# Synth.net
KiCad netlist of a schematic drawn in Altium Designer
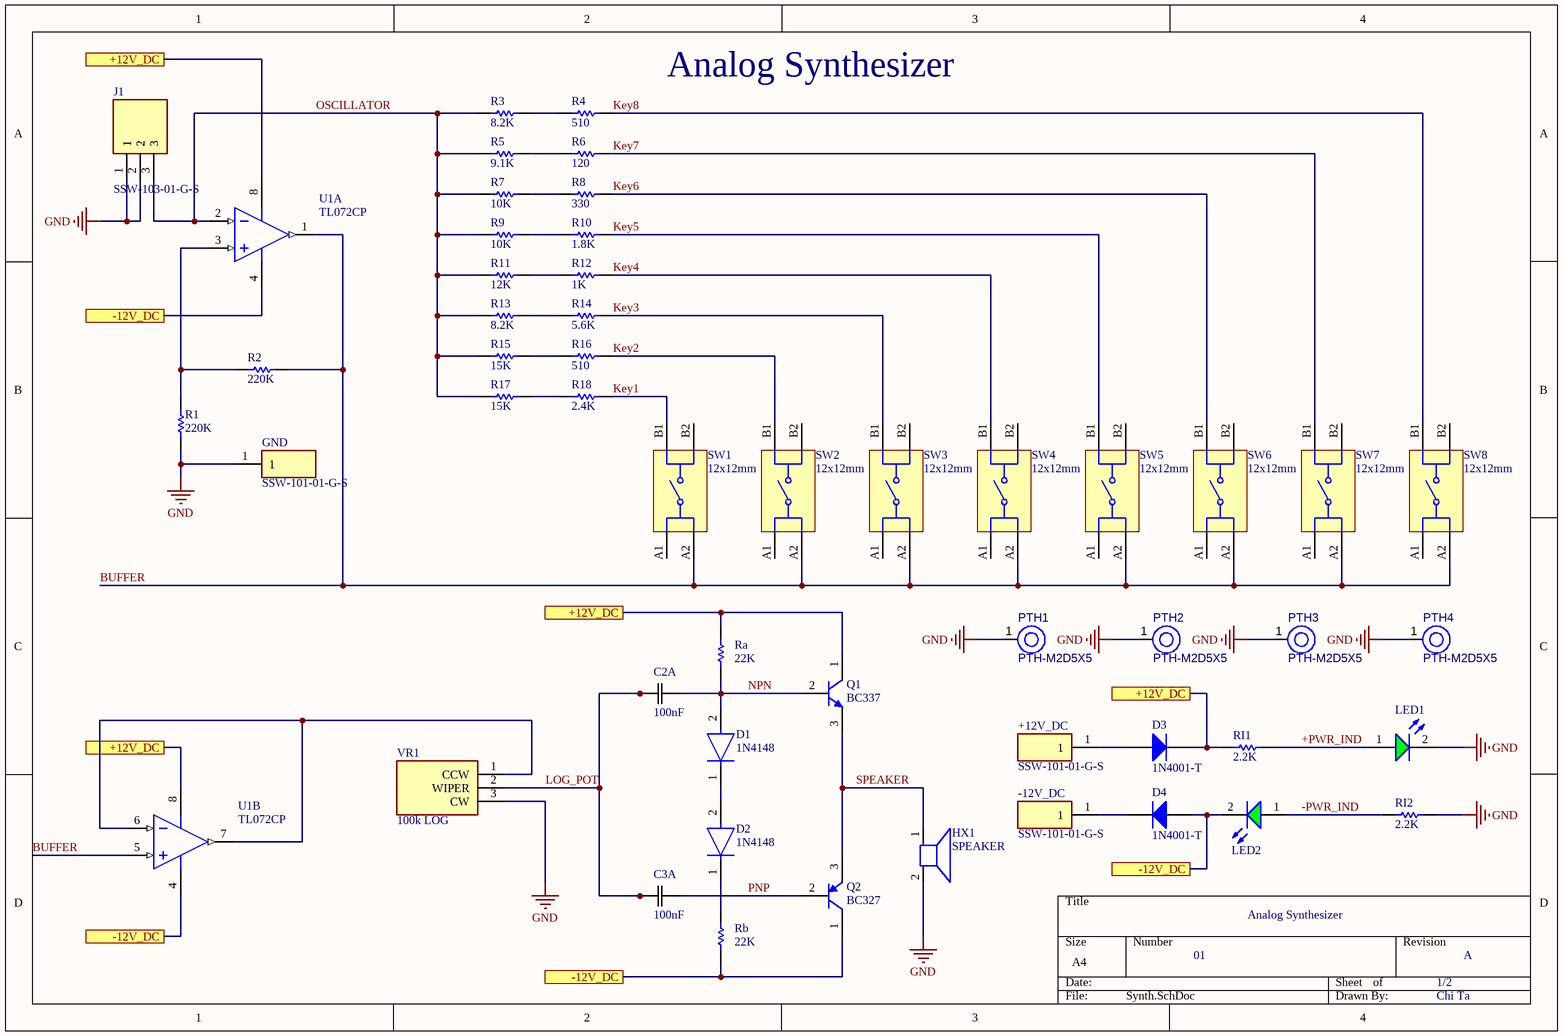
[diagram p0: Synth.SchDoc]

(export (version "E")
  (design (tool "Eeschema 10.0.6"))
  (components
    (comp (ref "+12V_DC")
      (value "SSW-101-01-G-S")
      (footprint "SamacSys:SSW-101-XX-YYY-S")
      (description "Connector")
      (fields (field (name "MOUSER PART NUMBER") "200-SSW10101GS"))
      (libsource (lib "*") (part "SSW-101-01-G-S"))
    )
    (comp (ref "-12V_DC")
      (value "SSW-101-01-G-S")
      (footprint "SamacSys:SSW-101-XX-YYY-S")
      (description "Connector")
      (fields (field (name "MOUSER PART NUMBER") "200-SSW10101GS"))
      (libsource (lib "*") (part "SSW-101-01-G-S"))
    )
    (comp (ref "C2")
      (value "100nF")
      (footprint "CAP_MKT1817_7p2x2p5x6p5-5_VIS")
      (description "MKT1817410064W")
      (libsource (lib "TMU") (part "MKT1817410064W"))
    )
    (comp (ref "C3")
      (value "100nF")
      (footprint "CAP_MKT1817_7p2x2p5x6p5-5_VIS")
      (description "MKT1817410064W")
      (libsource (lib "TMU") (part "MKT1817410064W"))
    )
    (comp (ref "D1")
      (value "1N4148")
      (footprint "FP-017AG-MFG")
      (description "DIODE GEN PURP 100V 200MA DO35")
      (fields (field (name "VOLTAGE") "100V"))
      (libsource (lib "Altium Content Vault") (part "d7152d700b627762746794eb795d46e"))
    )
    (comp (ref "D2")
      (value "1N4148")
      (footprint "FP-017AG-MFG")
      (description "DIODE GEN PURP 100V 200MA DO35")
      (fields (field (name "VOLTAGE") "100V"))
      (libsource (lib "Altium Content Vault") (part "d7152d700b627762746794eb795d46e"))
    )
    (comp (ref "D3")
      (value "1N4001-T")
      (footprint "DIOD-DO-41-P-2_V")
      (description "1.0 A Rectifier, 15 pF, 50 V, -65 to 150 degC, 2-Pin DO-41 Plastic, RoHS, Tape and Reel")
      (fields (field (name "MANUFACTURER") "Diodes Inc"))
      (libsource (lib "Altium Content Vault") (part "DIOD-D-A1K2-2"))
    )
    (comp (ref "D4")
      (value "1N4001-T")
      (footprint "DIOD-DO-41-P-2_V")
      (description "1.0 A Rectifier, 15 pF, 50 V, -65 to 150 degC, 2-Pin DO-41 Plastic, RoHS, Tape and Reel")
      (fields (field (name "MANUFACTURER") "Diodes Inc"))
      (libsource (lib "Altium Content Vault") (part "DIOD-D-A1K2-2"))
    )
    (comp (ref "GND")
      (value "SSW-101-01-G-S")
      (footprint "SamacSys:SSW-101-XX-YYY-S")
      (description "Connector")
      (fields (field (name "MOUSER PART NUMBER") "200-SSW10101GS"))
      (libsource (lib "") (part "SSW-101-01-G-S_1"))
    )
    (comp (ref "HX1")
      (value "SPEAKER")
      (footprint "AL60P")
      (description "8 Ohms Low Profile Speaker 250mW 380Hz ~ 10kHz Top Round 93dB")
      (fields (field (name "MF") "Texas Instruments"))
      (libsource (lib "TMU") (part "SPEAKER"))
    )
    (comp (ref "J1")
      (value "SSW-103-01-G-S")
      (footprint "SamacSys:RHDR3W64P0X254_1X3_813X241X851P")
      (description "Connector")
      (fields (field (name "MOUSER PART NUMBER") "200-SSW10301GS"))
      (libsource (lib "*") (part "SSW-103-01-G-S"))
    )
    (comp (ref "LED1")
      (value "151031VS04000")
      (footprint "WL-TMRC_D3.95H5.3")
      (libsource (lib "Altium Content Vault") (part "LED_Green_1A-2K"))
    )
    (comp (ref "LED2")
      (value "151031VS04000")
      (footprint "WL-TMRC_D3.95H5.3")
      (libsource (lib "Altium Content Vault") (part "LED_Green_1A-2K"))
    )
    (comp (ref "PTH1")
      (value "PTH-M2D5X5")
      (footprint "PTH-M2D5X5")
      (description "M2 PTH (2.5mm), 5mm pad")
      (libsource (lib "TMU") (part "CMP-00028-00000-1"))
    )
    (comp (ref "PTH2")
      (value "PTH-M2D5X5")
      (footprint "PTH-M2D5X5")
      (description "M2 PTH (2.5mm), 5mm pad")
      (libsource (lib "TMU") (part "CMP-00028-00000-1"))
    )
    (comp (ref "PTH3")
      (value "PTH-M2D5X5")
      (footprint "PTH-M2D5X5")
      (description "M2 PTH (2.5mm), 5mm pad")
      (libsource (lib "TMU") (part "CMP-00028-00000-1"))
    )
    (comp (ref "PTH4")
      (value "PTH-M2D5X5")
      (footprint "PTH-M2D5X5")
      (description "M2 PTH (2.5mm), 5mm pad")
      (libsource (lib "TMU") (part "CMP-00028-00000-1"))
    )
    (comp (ref "Q1")
      (value "BC337")
      (footprint "ONSC-TO-92-3-29-11_AM_BL")
      (description "Amplifier Transistor, NPN Silicon, 3-Pin TO-92, Pb-Free, Ammo Box")
      (fields (field (name "PARTNUMBER") "BC337-40ZL1G") (field (name "MANUFACTURER") "On Semiconductor"))
      (libsource (lib "Altium Content Vault") (part "ONSC-NPN-C1B2E3-3"))
    )
    (comp (ref "Q2")
      (value "BC327")
      (footprint "ONSC-TO-92-3-29-11_AM_BL")
      (description "Amplifier Transistor, PNP Silicon, 3-Pin TO-92, Pb-Free, Ammo Box")
      (fields (field (name "MANUFACTURER") "On Semiconductor") (field (name "PARTNUMBER") "BC327-25ZL1G"))
      (libsource (lib "Altium Content Vault") (part "ONSC-PNP-C1B2E3-3"))
    )
    (comp (ref "R1")
      (value "220K")
      (footprint "RESA60-630X240")
      (description "Axial Resistor, 10 KOhm, +/- 1%, 0.25 W, -55 to 155 degC, 2-Pin THD, RoHS, Bulk")
      (fields (field (name "TOLERANCE") "1%") (field (name "MANUFACTURER") "Yageo"))
      (libsource (lib "Altium Content Vault") (part "RES-2"))
    )
    (comp (ref "R2")
      (value "220K")
      (footprint "RESA60-630X240")
      (description "Axial Resistor, 10 KOhm, +/- 1%, 0.25 W, -55 to 155 degC, 2-Pin THD, RoHS, Bulk")
      (fields (field (name "TOLERANCE") "1%") (field (name "MANUFACTURER") "Yageo"))
      (libsource (lib "Altium Content Vault") (part "RES-2"))
    )
    (comp (ref "R3")
      (value "8.2K")
      (footprint "RESA60-630X240")
      (description "Axial Resistor, 10 KOhm, +/- 1%, 0.25 W, -55 to 155 degC, 2-Pin THD, RoHS, Bulk")
      (fields (field (name "TOLERANCE") "1%") (field (name "MANUFACTURER") "Yageo"))
      (libsource (lib "Altium Content Vault") (part "RES-2"))
    )
    (comp (ref "R4")
      (value "510")
      (footprint "RESA60-630X240")
      (description "Axial Resistor, 10 KOhm, +/- 1%, 0.25 W, -55 to 155 degC, 2-Pin THD, RoHS, Bulk")
      (fields (field (name "TOLERANCE") "1%") (field (name "MANUFACTURER") "Yageo"))
      (libsource (lib "Altium Content Vault") (part "RES-2"))
    )
    (comp (ref "R5")
      (value "9.1K")
      (footprint "RESA60-630X240")
      (description "Axial Resistor, 10 KOhm, +/- 1%, 0.25 W, -55 to 155 degC, 2-Pin THD, RoHS, Bulk")
      (fields (field (name "TOLERANCE") "1%") (field (name "MANUFACTURER") "Yageo"))
      (libsource (lib "Altium Content Vault") (part "RES-2"))
    )
    (comp (ref "R6")
      (value "120")
      (footprint "RESA60-630X240")
      (description "Axial Resistor, 10 KOhm, +/- 1%, 0.25 W, -55 to 155 degC, 2-Pin THD, RoHS, Bulk")
      (fields (field (name "TOLERANCE") "1%") (field (name "MANUFACTURER") "Yageo"))
      (libsource (lib "Altium Content Vault") (part "RES-2"))
    )
    (comp (ref "R7")
      (value "10K")
      (footprint "RESA60-630X240")
      (description "Axial Resistor, 10 KOhm, +/- 1%, 0.25 W, -55 to 155 degC, 2-Pin THD, RoHS, Bulk")
      (fields (field (name "TOLERANCE") "1%") (field (name "MANUFACTURER") "Yageo"))
      (libsource (lib "Altium Content Vault") (part "RES-2"))
    )
    (comp (ref "R8")
      (value "330")
      (footprint "RESA60-630X240")
      (description "Axial Resistor, 10 KOhm, +/- 1%, 0.25 W, -55 to 155 degC, 2-Pin THD, RoHS, Bulk")
      (fields (field (name "TOLERANCE") "1%") (field (name "MANUFACTURER") "Yageo"))
      (libsource (lib "Altium Content Vault") (part "RES-2"))
    )
    (comp (ref "R9")
      (value "10K")
      (footprint "RESA60-630X240")
      (description "Axial Resistor, 10 KOhm, +/- 1%, 0.25 W, -55 to 155 degC, 2-Pin THD, RoHS, Bulk")
      (fields (field (name "TOLERANCE") "1%") (field (name "MANUFACTURER") "Yageo"))
      (libsource (lib "Altium Content Vault") (part "RES-2"))
    )
    (comp (ref "R10")
      (value "1.8K")
      (footprint "RESA60-630X240")
      (description "Axial Resistor, 10 KOhm, +/- 1%, 0.25 W, -55 to 155 degC, 2-Pin THD, RoHS, Bulk")
      (fields (field (name "TOLERANCE") "1%") (field (name "MANUFACTURER") "Yageo"))
      (libsource (lib "Altium Content Vault") (part "RES-2"))
    )
    (comp (ref "R11")
      (value "12K")
      (footprint "RESA60-630X240")
      (description "Axial Resistor, 10 KOhm, +/- 1%, 0.25 W, -55 to 155 degC, 2-Pin THD, RoHS, Bulk")
      (fields (field (name "TOLERANCE") "1%") (field (name "MANUFACTURER") "Yageo"))
      (libsource (lib "Altium Content Vault") (part "RES-2"))
    )
    (comp (ref "R12")
      (value "1K")
      (footprint "RESA60-630X240")
      (description "Axial Resistor, 10 KOhm, +/- 1%, 0.25 W, -55 to 155 degC, 2-Pin THD, RoHS, Bulk")
      (fields (field (name "TOLERANCE") "1%") (field (name "MANUFACTURER") "Yageo"))
      (libsource (lib "Altium Content Vault") (part "RES-2"))
    )
    (comp (ref "R13")
      (value "8.2K")
      (footprint "RESA60-630X240")
      (description "Axial Resistor, 10 KOhm, +/- 1%, 0.25 W, -55 to 155 degC, 2-Pin THD, RoHS, Bulk")
      (fields (field (name "TOLERANCE") "1%") (field (name "MANUFACTURER") "Yageo"))
      (libsource (lib "Altium Content Vault") (part "RES-2"))
    )
    (comp (ref "R14")
      (value "5.6K")
      (footprint "RESA60-630X240")
      (description "Axial Resistor, 10 KOhm, +/- 1%, 0.25 W, -55 to 155 degC, 2-Pin THD, RoHS, Bulk")
      (fields (field (name "TOLERANCE") "1%") (field (name "MANUFACTURER") "Yageo"))
      (libsource (lib "Altium Content Vault") (part "RES-2"))
    )
    (comp (ref "R15")
      (value "15K")
      (footprint "RESA60-630X240")
      (description "Axial Resistor, 10 KOhm, +/- 1%, 0.25 W, -55 to 155 degC, 2-Pin THD, RoHS, Bulk")
      (fields (field (name "TOLERANCE") "1%") (field (name "MANUFACTURER") "Yageo"))
      (libsource (lib "Altium Content Vault") (part "RES-2"))
    )
    (comp (ref "R16")
      (value "510")
      (footprint "RESA60-630X240")
      (description "Axial Resistor, 10 KOhm, +/- 1%, 0.25 W, -55 to 155 degC, 2-Pin THD, RoHS, Bulk")
      (fields (field (name "TOLERANCE") "1%") (field (name "MANUFACTURER") "Yageo"))
      (libsource (lib "Altium Content Vault") (part "RES-2"))
    )
    (comp (ref "R17")
      (value "15K")
      (footprint "RESA60-630X240")
      (description "Axial Resistor, 10 KOhm, +/- 1%, 0.25 W, -55 to 155 degC, 2-Pin THD, RoHS, Bulk")
      (fields (field (name "TOLERANCE") "1%") (field (name "MANUFACTURER") "Yageo"))
      (libsource (lib "Altium Content Vault") (part "RES-2"))
    )
    (comp (ref "R18")
      (value "2.4K")
      (footprint "RESA60-630X240")
      (description "Axial Resistor, 10 KOhm, +/- 1%, 0.25 W, -55 to 155 degC, 2-Pin THD, RoHS, Bulk")
      (fields (field (name "TOLERANCE") "1%") (field (name "MANUFACTURER") "Yageo"))
      (libsource (lib "Altium Content Vault") (part "RES-2"))
    )
    (comp (ref "Ra")
      (value "22K")
      (footprint "RESA60-630X240")
      (description "Axial Resistor, 10 KOhm, +/- 1%, 0.25 W, -55 to 155 degC, 2-Pin THD, RoHS, Bulk")
      (fields (field (name "TOLERANCE") "1%") (field (name "MANUFACTURER") "Yageo"))
      (libsource (lib "Altium Content Vault") (part "RES-2"))
    )
    (comp (ref "Rb")
      (value "22K")
      (footprint "RESA60-630X240")
      (description "Axial Resistor, 10 KOhm, +/- 1%, 0.25 W, -55 to 155 degC, 2-Pin THD, RoHS, Bulk")
      (fields (field (name "TOLERANCE") "1%") (field (name "MANUFACTURER") "Yageo"))
      (libsource (lib "Altium Content Vault") (part "RES-2"))
    )
    (comp (ref "RI1")
      (value "2.2K")
      (footprint "RESA60-630X240")
      (description "Axial Resistor, 10 KOhm, +/- 1%, 0.25 W, -55 to 155 degC, 2-Pin THD, RoHS, Bulk")
      (fields (field (name "TOLERANCE") "1%") (field (name "MANUFACTURER") "Yageo"))
      (libsource (lib "Altium Content Vault") (part "RES-2"))
    )
    (comp (ref "RI2")
      (value "2.2K")
      (footprint "RESA60-630X240")
      (description "Axial Resistor, 10 KOhm, +/- 1%, 0.25 W, -55 to 155 degC, 2-Pin THD, RoHS, Bulk")
      (fields (field (name "TOLERANCE") "1%") (field (name "MANUFACTURER") "Yageo"))
      (libsource (lib "Altium Content Vault") (part "RES-2"))
    )
    (comp (ref "SW1")
      (value "12x12mm")
      (footprint "4304x60857x6")
      (libsource (lib "Altium Content Vault") (part "SPST-NO_4P"))
    )
    (comp (ref "SW2")
      (value "12x12mm")
      (footprint "4304x60857x6")
      (libsource (lib "Altium Content Vault") (part "SPST-NO_4P"))
    )
    (comp (ref "SW3")
      (value "12x12mm")
      (footprint "4304x60857x6")
      (libsource (lib "Altium Content Vault") (part "SPST-NO_4P"))
    )
    (comp (ref "SW4")
      (value "12x12mm")
      (footprint "4304x60857x6")
      (libsource (lib "Altium Content Vault") (part "SPST-NO_4P"))
    )
    (comp (ref "SW5")
      (value "12x12mm")
      (footprint "4304x60857x6")
      (libsource (lib "Altium Content Vault") (part "SPST-NO_4P"))
    )
    (comp (ref "SW6")
      (value "12x12mm")
      (footprint "4304x60857x6")
      (libsource (lib "Altium Content Vault") (part "SPST-NO_4P"))
    )
    (comp (ref "SW7")
      (value "12x12mm")
      (footprint "4304x60857x6")
      (libsource (lib "Altium Content Vault") (part "SPST-NO_4P"))
    )
    (comp (ref "SW8")
      (value "12x12mm")
      (footprint "4304x60857x6")
      (libsource (lib "Altium Content Vault") (part "SPST-NO_4P"))
    )
    (comp (ref "U1")
      (value "TL072CP")
      (footprint "P0008A")
      (fields (field (name "MANUFACTURER") "Texas Instruments"))
      (libsource (lib "Altium Content Vault") (part "TI-AMP-D6-2-8_D"))
    )
    (comp (ref "VR1")
      (value "100k LOG")
      (footprint "SamacSys:PDB181K420K104A2")
      (description "Variable Resistor PDB181-K420K-104A2")
      (fields
        (field (name "MANUFACTURER_PART_NUMBER") "PDB181-K420K-104A2")
        (field (name "MOUSER PART NUMBER") "652-PDB181K420K104A2")
      )
      (libsource (lib "*") (part "PDB181-K420K-104A2"))
    )
  )
  (nets
    (net (code "1") (name "/+12V_DC") (class "Default")
      (node (ref "D3") (pin "2") (pinfunction "K_2") (pintype "passive"))
      (node (ref "Q1") (pin "1") (pinfunction "C_1") (pintype "passive"))
      (node (ref "RI1") (pin "1") (pinfunction "1_1") (pintype "passive"))
      (node (ref "Ra") (pin "2") (pinfunction "2_2") (pintype "passive"))
      (node (ref "U1") (pin "8") (pinfunction "VCC+_8") (pintype "power_in"))
    )
    (net (code "2") (name "/+PWR_IND") (class "Default")
      (node (ref "LED1") (pin "1") (pinfunction "A_1") (pintype "passive"))
      (node (ref "RI1") (pin "2") (pinfunction "2_2") (pintype "passive"))
    )
    (net (code "3") (name "/-12V_DC") (class "Default")
      (node (ref "D4") (pin "1") (pinfunction "A_1") (pintype "passive"))
      (node (ref "LED2") (pin "2") (pinfunction "K_2") (pintype "passive"))
      (node (ref "Q2") (pin "1") (pinfunction "C_1") (pintype "passive"))
      (node (ref "Rb") (pin "1") (pinfunction "1_1") (pintype "passive"))
      (node (ref "U1") (pin "4") (pinfunction "VCC-_4") (pintype "power_in"))
    )
    (net (code "4") (name "/-PWR_IND") (class "Default")
      (node (ref "LED2") (pin "1") (pinfunction "A_1") (pintype "passive"))
      (node (ref "RI2") (pin "2") (pinfunction "2_2") (pintype "passive"))
    )
    (net (code "5") (name "/BUFFER") (class "Default")
      (node (ref "R2") (pin "2") (pinfunction "2_2") (pintype "passive"))
      (node (ref "SW1") (pin "A2") (pinfunction "A2_A2") (pintype "passive"))
      (node (ref "SW2") (pin "A2") (pinfunction "A2_A2") (pintype "passive"))
      (node (ref "SW3") (pin "A2") (pinfunction "A2_A2") (pintype "passive"))
      (node (ref "SW4") (pin "A2") (pinfunction "A2_A2") (pintype "passive"))
      (node (ref "SW5") (pin "A2") (pinfunction "A2_A2") (pintype "passive"))
      (node (ref "SW6") (pin "A2") (pinfunction "A2_A2") (pintype "passive"))
      (node (ref "SW7") (pin "A2") (pinfunction "A2_A2") (pintype "passive"))
      (node (ref "SW8") (pin "A2") (pinfunction "A2_A2") (pintype "passive"))
      (node (ref "U1") (pin "1") (pinfunction "OUT1_1") (pintype "output"))
      (node (ref "U1") (pin "5") (pinfunction "IN2+_5") (pintype "input"))
    )
    (net (code "6") (name "/Key1") (class "Default")
      (node (ref "R18") (pin "2") (pinfunction "2_2") (pintype "passive"))
      (node (ref "SW1") (pin "B1") (pinfunction "B1_B1") (pintype "passive"))
    )
    (net (code "7") (name "/Key2") (class "Default")
      (node (ref "R16") (pin "2") (pinfunction "2_2") (pintype "passive"))
      (node (ref "SW2") (pin "B1") (pinfunction "B1_B1") (pintype "passive"))
    )
    (net (code "8") (name "/Key3") (class "Default")
      (node (ref "R14") (pin "2") (pinfunction "2_2") (pintype "passive"))
      (node (ref "SW3") (pin "B1") (pinfunction "B1_B1") (pintype "passive"))
    )
    (net (code "9") (name "/Key4") (class "Default")
      (node (ref "R12") (pin "2") (pinfunction "2_2") (pintype "passive"))
      (node (ref "SW4") (pin "B1") (pinfunction "B1_B1") (pintype "passive"))
    )
    (net (code "10") (name "/Key5") (class "Default")
      (node (ref "R10") (pin "2") (pinfunction "2_2") (pintype "passive"))
      (node (ref "SW5") (pin "B1") (pinfunction "B1_B1") (pintype "passive"))
    )
    (net (code "11") (name "/Key6") (class "Default")
      (node (ref "R8") (pin "2") (pinfunction "2_2") (pintype "passive"))
      (node (ref "SW6") (pin "B1") (pinfunction "B1_B1") (pintype "passive"))
    )
    (net (code "12") (name "/Key7") (class "Default")
      (node (ref "R6") (pin "2") (pinfunction "2_2") (pintype "passive"))
      (node (ref "SW7") (pin "B1") (pinfunction "B1_B1") (pintype "passive"))
    )
    (net (code "13") (name "/Key8") (class "Default")
      (node (ref "R4") (pin "2") (pinfunction "2_2") (pintype "passive"))
      (node (ref "SW8") (pin "B1") (pinfunction "B1_B1") (pintype "passive"))
    )
    (net (code "14") (name "/LOG_POT") (class "Default")
      (node (ref "C2") (pin "1") (pinfunction "1_1") (pintype "passive"))
      (node (ref "C3") (pin "1") (pinfunction "1_1") (pintype "passive"))
      (node (ref "VR1") (pin "2") (pinfunction "WIPER_2") (pintype "passive"))
    )
    (net (code "15") (name "/NPN") (class "Default")
      (node (ref "C2") (pin "2") (pinfunction "2_2") (pintype "passive"))
      (node (ref "D1") (pin "2") (pinfunction "A_2") (pintype "passive"))
      (node (ref "Q1") (pin "2") (pinfunction "B_2") (pintype "passive"))
      (node (ref "Ra") (pin "1") (pinfunction "1_1") (pintype "passive"))
    )
    (net (code "16") (name "/OSCILLATOR") (class "Default")
      (node (ref "J1") (pin "3") (pinfunction "3_3") (pintype "passive"))
      (node (ref "R11") (pin "1") (pinfunction "1_1") (pintype "passive"))
      (node (ref "R13") (pin "1") (pinfunction "1_1") (pintype "passive"))
      (node (ref "R15") (pin "1") (pinfunction "1_1") (pintype "passive"))
      (node (ref "R17") (pin "1") (pinfunction "1_1") (pintype "passive"))
      (node (ref "R3") (pin "1") (pinfunction "1_1") (pintype "passive"))
      (node (ref "R5") (pin "1") (pinfunction "1_1") (pintype "passive"))
      (node (ref "R7") (pin "1") (pinfunction "1_1") (pintype "passive"))
      (node (ref "R9") (pin "1") (pinfunction "1_1") (pintype "passive"))
      (node (ref "U1") (pin "2") (pinfunction "IN1-_2") (pintype "input"))
    )
    (net (code "17") (name "/PNP") (class "Default")
      (node (ref "C3") (pin "2") (pinfunction "2_2") (pintype "passive"))
      (node (ref "Q2") (pin "2") (pinfunction "B_2") (pintype "passive"))
    )
    (net (code "18") (name "/SPEAKER") (class "Default")
      (node (ref "HX1") (pin "1") (pinfunction "POS_1") (pintype "passive"))
      (node (ref "Q1") (pin "3") (pinfunction "E_3") (pintype "passive"))
      (node (ref "Q2") (pin "3") (pinfunction "E_3") (pintype "passive"))
    )
    (net (code "19") (name "GND") (class "Default")
      (node (ref "GND") (pin "1") (pinfunction "1_1") (pintype "passive"))
      (node (ref "HX1") (pin "2") (pinfunction "NEG_2") (pintype "passive"))
      (node (ref "J1") (pin "1") (pinfunction "1_1") (pintype "passive"))
      (node (ref "J1") (pin "2") (pinfunction "2_2") (pintype "passive"))
      (node (ref "LED1") (pin "2") (pinfunction "K_2") (pintype "passive"))
      (node (ref "PTH1") (pin "1") (pinfunction "H1_1") (pintype "passive"))
      (node (ref "PTH2") (pin "1") (pinfunction "H1_1") (pintype "passive"))
      (node (ref "PTH3") (pin "1") (pinfunction "H1_1") (pintype "passive"))
      (node (ref "PTH4") (pin "1") (pinfunction "H1_1") (pintype "passive"))
      (node (ref "R1") (pin "1") (pinfunction "1_1") (pintype "passive"))
      (node (ref "RI2") (pin "1") (pinfunction "1_1") (pintype "passive"))
      (node (ref "VR1") (pin "3") (pinfunction "CW_3") (pintype "passive"))
    )
    (net (code "20") (name "Net-(D1-C)") (class "Default")
      (node (ref "D1") (pin "1") (pinfunction "C_1") (pintype "passive"))
      (node (ref "D2") (pin "2") (pinfunction "A_2") (pintype "passive"))
    )
    (net (code "21") (name "Net-(D2-C)") (class "Default")
      (node (ref "D2") (pin "1") (pinfunction "C_1") (pintype "passive"))
      (node (ref "Rb") (pin "2") (pinfunction "2_2") (pintype "passive"))
    )
    (net (code "22") (name "Net-(D3-A)") (class "Default")
      (node (ref "+12V_DC") (pin "1") (pinfunction "1_1") (pintype "passive"))
      (node (ref "D3") (pin "1") (pinfunction "A_1") (pintype "passive"))
    )
    (net (code "23") (name "Net-(D4-K)") (class "Default")
      (node (ref "-12V_DC") (pin "1") (pinfunction "1_1") (pintype "passive"))
      (node (ref "D4") (pin "2") (pinfunction "K_2") (pintype "passive"))
    )
    (net (code "24") (name "Net-(R3-Pad2)") (class "Default")
      (node (ref "R3") (pin "2") (pinfunction "2_2") (pintype "passive"))
      (node (ref "R4") (pin "1") (pinfunction "1_1") (pintype "passive"))
    )
    (net (code "25") (name "Net-(R5-Pad2)") (class "Default")
      (node (ref "R5") (pin "2") (pinfunction "2_2") (pintype "passive"))
      (node (ref "R6") (pin "1") (pinfunction "1_1") (pintype "passive"))
    )
    (net (code "26") (name "Net-(R7-Pad2)") (class "Default")
      (node (ref "R7") (pin "2") (pinfunction "2_2") (pintype "passive"))
      (node (ref "R8") (pin "1") (pinfunction "1_1") (pintype "passive"))
    )
    (net (code "27") (name "Net-(R10-Pad1)") (class "Default")
      (node (ref "R10") (pin "1") (pinfunction "1_1") (pintype "passive"))
      (node (ref "R9") (pin "2") (pinfunction "2_2") (pintype "passive"))
    )
    (net (code "28") (name "Net-(R11-Pad2)") (class "Default")
      (node (ref "R11") (pin "2") (pinfunction "2_2") (pintype "passive"))
      (node (ref "R12") (pin "1") (pinfunction "1_1") (pintype "passive"))
    )
    (net (code "29") (name "Net-(R13-Pad2)") (class "Default")
      (node (ref "R13") (pin "2") (pinfunction "2_2") (pintype "passive"))
      (node (ref "R14") (pin "1") (pinfunction "1_1") (pintype "passive"))
    )
    (net (code "30") (name "Net-(R15-Pad2)") (class "Default")
      (node (ref "R15") (pin "2") (pinfunction "2_2") (pintype "passive"))
      (node (ref "R16") (pin "1") (pinfunction "1_1") (pintype "passive"))
    )
    (net (code "31") (name "Net-(R17-Pad2)") (class "Default")
      (node (ref "R17") (pin "2") (pinfunction "2_2") (pintype "passive"))
      (node (ref "R18") (pin "1") (pinfunction "1_1") (pintype "passive"))
    )
    (net (code "32") (name "Net-(U1A-IN1+)") (class "Default")
      (node (ref "R1") (pin "2") (pinfunction "2_2") (pintype "passive"))
      (node (ref "R2") (pin "1") (pinfunction "1_1") (pintype "passive"))
      (node (ref "U1") (pin "3") (pinfunction "IN1+_3") (pintype "input"))
    )
    (net (code "33") (name "Net-(U1B-IN2-)") (class "Default")
      (node (ref "U1") (pin "6") (pinfunction "IN2-_6") (pintype "input"))
      (node (ref "U1") (pin "7") (pinfunction "OUT2_7") (pintype "output"))
      (node (ref "VR1") (pin "1") (pinfunction "CCW_1") (pintype "passive"))
    )
    (net (code "34") (name "unconnected-(SW1-PadA1)") (class "Default")
      (node (ref "SW1") (pin "A1") (pinfunction "A1_A1") (pintype "passive"))
    )
    (net (code "35") (name "unconnected-(SW1-PadB2)") (class "Default")
      (node (ref "SW1") (pin "B2") (pinfunction "B2_B2") (pintype "passive"))
    )
    (net (code "36") (name "unconnected-(SW2-PadA1)") (class "Default")
      (node (ref "SW2") (pin "A1") (pinfunction "A1_A1") (pintype "passive"))
    )
    (net (code "37") (name "unconnected-(SW2-PadB2)") (class "Default")
      (node (ref "SW2") (pin "B2") (pinfunction "B2_B2") (pintype "passive"))
    )
    (net (code "38") (name "unconnected-(SW3-PadA1)") (class "Default")
      (node (ref "SW3") (pin "A1") (pinfunction "A1_A1") (pintype "passive"))
    )
    (net (code "39") (name "unconnected-(SW3-PadB2)") (class "Default")
      (node (ref "SW3") (pin "B2") (pinfunction "B2_B2") (pintype "passive"))
    )
    (net (code "40") (name "unconnected-(SW4-PadA1)") (class "Default")
      (node (ref "SW4") (pin "A1") (pinfunction "A1_A1") (pintype "passive"))
    )
    (net (code "41") (name "unconnected-(SW4-PadB2)") (class "Default")
      (node (ref "SW4") (pin "B2") (pinfunction "B2_B2") (pintype "passive"))
    )
    (net (code "42") (name "unconnected-(SW5-PadA1)") (class "Default")
      (node (ref "SW5") (pin "A1") (pinfunction "A1_A1") (pintype "passive"))
    )
    (net (code "43") (name "unconnected-(SW5-PadB2)") (class "Default")
      (node (ref "SW5") (pin "B2") (pinfunction "B2_B2") (pintype "passive"))
    )
    (net (code "44") (name "unconnected-(SW6-PadA1)") (class "Default")
      (node (ref "SW6") (pin "A1") (pinfunction "A1_A1") (pintype "passive"))
    )
    (net (code "45") (name "unconnected-(SW6-PadB2)") (class "Default")
      (node (ref "SW6") (pin "B2") (pinfunction "B2_B2") (pintype "passive"))
    )
    (net (code "46") (name "unconnected-(SW7-PadA1)") (class "Default")
      (node (ref "SW7") (pin "A1") (pinfunction "A1_A1") (pintype "passive"))
    )
    (net (code "47") (name "unconnected-(SW7-PadB2)") (class "Default")
      (node (ref "SW7") (pin "B2") (pinfunction "B2_B2") (pintype "passive"))
    )
    (net (code "48") (name "unconnected-(SW8-PadA1)") (class "Default")
      (node (ref "SW8") (pin "A1") (pinfunction "A1_A1") (pintype "passive"))
    )
    (net (code "49") (name "unconnected-(SW8-PadB2)") (class "Default")
      (node (ref "SW8") (pin "B2") (pinfunction "B2_B2") (pintype "passive"))
    )
  )
)
